# 03_-_CONNECTORS.net
KiCad netlist of a schematic drawn in Altium Designer
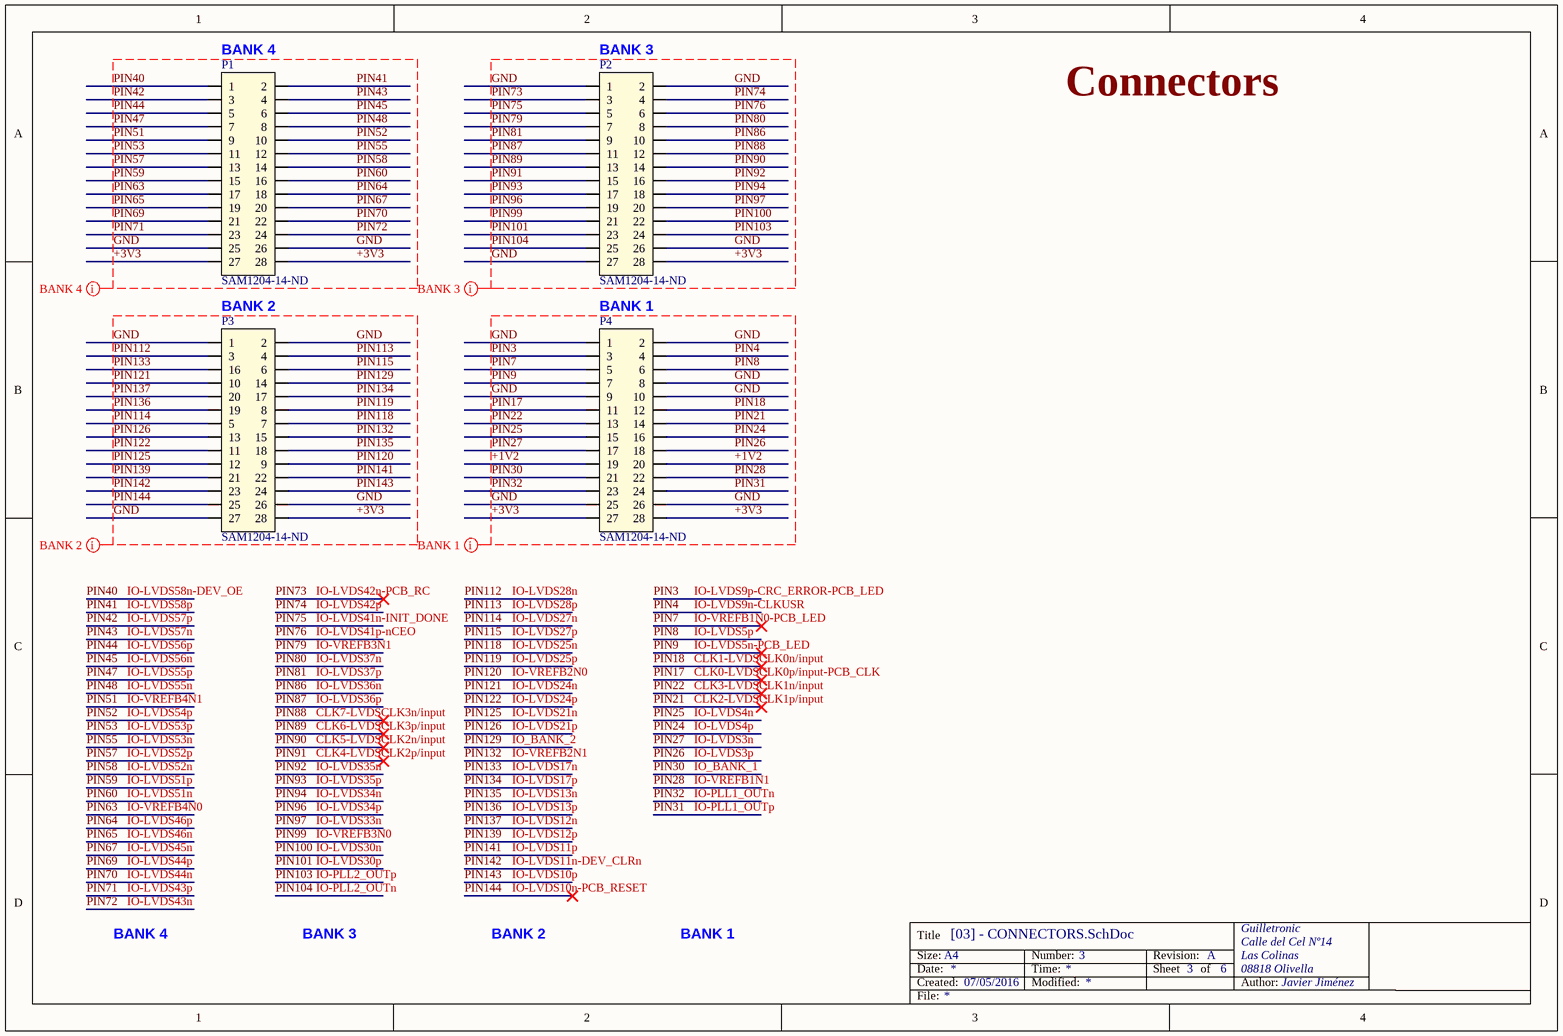
[diagram p0: [03] - CONNECTORS.SchDoc]

(export (version "E")
  (design (tool "Eeschema 10.0.6"))
  (components
    (comp (ref "P1")
      (value "Female Header 14x2 2.54mm 10mm")
      (footprint "Female Header 14x2 2.54mm 10mm")
      (description "ELEVATED SOCKET STRIPS")
      (fields (field (name "SUPPLIER PART NUMBER 1") "SAM1204-14-ND"))
      (libsource (lib "GUILLETRONIC") (part "Female Header 14x2 2.54mm 10mm"))
    )
    (comp (ref "P2")
      (value "Female Header 14x2 2.54mm 10mm")
      (footprint "Female Header 14x2 2.54mm 10mm")
      (description "ELEVATED SOCKET STRIPS")
      (fields (field (name "SUPPLIER PART NUMBER 1") "SAM1204-14-ND"))
      (libsource (lib "GUILLETRONIC") (part "Female Header 14x2 2.54mm 10mm"))
    )
    (comp (ref "P3")
      (value "Female Header 14x2 2.54mm 10mm")
      (footprint "Female Header 14x2 2.54mm 10mm")
      (description "ELEVATED SOCKET STRIPS")
      (fields (field (name "SUPPLIER PART NUMBER 1") "SAM1204-14-ND"))
      (libsource (lib "") (part "Female Header 14x2 2.54mm 10mm_1"))
    )
    (comp (ref "P4")
      (value "Female Header 14x2 2.54mm 10mm")
      (footprint "Female Header 14x2 2.54mm 10mm")
      (description "ELEVATED SOCKET STRIPS")
      (fields (field (name "SUPPLIER PART NUMBER 1") "SAM1204-14-ND"))
      (libsource (lib "GUILLETRONIC") (part "Female Header 14x2 2.54mm 10mm"))
    )
  )
  (nets
    (net (code "1") (name "/+1V2") (class "Default")
      (node (ref "P4") (pin "19") (pinfunction "19_19") (pintype "passive"))
      (node (ref "P4") (pin "20") (pinfunction "20_20") (pintype "passive"))
    )
    (net (code "2") (name "/+3V3") (class "Default")
      (node (ref "P1") (pin "27") (pinfunction "27_27") (pintype "passive"))
      (node (ref "P1") (pin "28") (pinfunction "28_28") (pintype "passive"))
      (node (ref "P2") (pin "28") (pinfunction "28_28") (pintype "passive"))
      (node (ref "P3") (pin "28") (pinfunction "28_28") (pintype "passive"))
      (node (ref "P4") (pin "27") (pinfunction "27_27") (pintype "passive"))
      (node (ref "P4") (pin "28") (pinfunction "28_28") (pintype "passive"))
    )
    (net (code "3") (name "/GND") (class "Default")
      (node (ref "P1") (pin "25") (pinfunction "25_25") (pintype "passive"))
      (node (ref "P1") (pin "26") (pinfunction "26_26") (pintype "passive"))
      (node (ref "P2") (pin "1") (pinfunction "1_1") (pintype "passive"))
      (node (ref "P2") (pin "2") (pinfunction "2_2") (pintype "passive"))
      (node (ref "P2") (pin "26") (pinfunction "26_26") (pintype "passive"))
      (node (ref "P2") (pin "27") (pinfunction "27_27") (pintype "passive"))
      (node (ref "P3") (pin "1") (pinfunction "1_1") (pintype "passive"))
      (node (ref "P3") (pin "2") (pinfunction "2_2") (pintype "passive"))
      (node (ref "P3") (pin "26") (pinfunction "26_26") (pintype "passive"))
      (node (ref "P3") (pin "27") (pinfunction "27_27") (pintype "passive"))
      (node (ref "P4") (pin "1") (pinfunction "1_1") (pintype "passive"))
      (node (ref "P4") (pin "10") (pinfunction "10_10") (pintype "passive"))
      (node (ref "P4") (pin "2") (pinfunction "2_2") (pintype "passive"))
      (node (ref "P4") (pin "25") (pinfunction "25_25") (pintype "passive"))
      (node (ref "P4") (pin "26") (pinfunction "26_26") (pintype "passive"))
      (node (ref "P4") (pin "8") (pinfunction "8_8") (pintype "passive"))
      (node (ref "P4") (pin "9") (pinfunction "9_9") (pintype "passive"))
    )
    (net (code "4") (name "/PIN3") (class "Default")
      (node (ref "P4") (pin "3") (pinfunction "3_3") (pintype "passive"))
    )
    (net (code "5") (name "/PIN4") (class "Default")
      (node (ref "P4") (pin "4") (pinfunction "4_4") (pintype "passive"))
    )
    (net (code "6") (name "/PIN7") (class "Default")
      (node (ref "P4") (pin "5") (pinfunction "5_5") (pintype "passive+no_connect"))
    )
    (net (code "7") (name "/PIN8") (class "Default")
      (node (ref "P4") (pin "6") (pinfunction "6_6") (pintype "passive"))
    )
    (net (code "8") (name "/PIN9") (class "Default")
      (node (ref "P4") (pin "7") (pinfunction "7_7") (pintype "passive+no_connect"))
    )
    (net (code "9") (name "/PIN17") (class "Default")
      (node (ref "P4") (pin "11") (pinfunction "11_11") (pintype "passive+no_connect"))
    )
    (net (code "10") (name "/PIN18") (class "Default")
      (node (ref "P4") (pin "12") (pinfunction "12_12") (pintype "passive+no_connect"))
    )
    (net (code "11") (name "/PIN21") (class "Default")
      (node (ref "P4") (pin "14") (pinfunction "14_14") (pintype "passive+no_connect"))
    )
    (net (code "12") (name "/PIN22") (class "Default")
      (node (ref "P4") (pin "13") (pinfunction "13_13") (pintype "passive+no_connect"))
    )
    (net (code "13") (name "/PIN24") (class "Default")
      (node (ref "P4") (pin "16") (pinfunction "16_16") (pintype "passive"))
    )
    (net (code "14") (name "/PIN25") (class "Default")
      (node (ref "P4") (pin "15") (pinfunction "15_15") (pintype "passive"))
    )
    (net (code "15") (name "/PIN26") (class "Default")
      (node (ref "P4") (pin "18") (pinfunction "18_18") (pintype "passive"))
    )
    (net (code "16") (name "/PIN27") (class "Default")
      (node (ref "P4") (pin "17") (pinfunction "17_17") (pintype "passive"))
    )
    (net (code "17") (name "/PIN28") (class "Default")
      (node (ref "P4") (pin "22") (pinfunction "22_22") (pintype "passive"))
    )
    (net (code "18") (name "/PIN30") (class "Default")
      (node (ref "P4") (pin "21") (pinfunction "21_21") (pintype "passive"))
    )
    (net (code "19") (name "/PIN31") (class "Default")
      (node (ref "P4") (pin "24") (pinfunction "24_24") (pintype "passive"))
    )
    (net (code "20") (name "/PIN32") (class "Default")
      (node (ref "P4") (pin "23") (pinfunction "23_23") (pintype "passive"))
    )
    (net (code "21") (name "/PIN40") (class "Default")
      (node (ref "P1") (pin "1") (pinfunction "1_1") (pintype "passive"))
    )
    (net (code "22") (name "/PIN41") (class "Default")
      (node (ref "P1") (pin "2") (pinfunction "2_2") (pintype "passive"))
    )
    (net (code "23") (name "/PIN42") (class "Default")
      (node (ref "P1") (pin "3") (pinfunction "3_3") (pintype "passive"))
    )
    (net (code "24") (name "/PIN43") (class "Default")
      (node (ref "P1") (pin "4") (pinfunction "4_4") (pintype "passive"))
    )
    (net (code "25") (name "/PIN44") (class "Default")
      (node (ref "P1") (pin "5") (pinfunction "5_5") (pintype "passive"))
    )
    (net (code "26") (name "/PIN45") (class "Default")
      (node (ref "P1") (pin "6") (pinfunction "6_6") (pintype "passive"))
    )
    (net (code "27") (name "/PIN47") (class "Default")
      (node (ref "P1") (pin "7") (pinfunction "7_7") (pintype "passive"))
    )
    (net (code "28") (name "/PIN48") (class "Default")
      (node (ref "P1") (pin "8") (pinfunction "8_8") (pintype "passive"))
    )
    (net (code "29") (name "/PIN51") (class "Default")
      (node (ref "P1") (pin "9") (pinfunction "9_9") (pintype "passive"))
    )
    (net (code "30") (name "/PIN52") (class "Default")
      (node (ref "P1") (pin "10") (pinfunction "10_10") (pintype "passive"))
    )
    (net (code "31") (name "/PIN53") (class "Default")
      (node (ref "P1") (pin "11") (pinfunction "11_11") (pintype "passive"))
    )
    (net (code "32") (name "/PIN55") (class "Default")
      (node (ref "P1") (pin "12") (pinfunction "12_12") (pintype "passive"))
    )
    (net (code "33") (name "/PIN57") (class "Default")
      (node (ref "P1") (pin "13") (pinfunction "13_13") (pintype "passive"))
    )
    (net (code "34") (name "/PIN58") (class "Default")
      (node (ref "P1") (pin "14") (pinfunction "14_14") (pintype "passive"))
    )
    (net (code "35") (name "/PIN59") (class "Default")
      (node (ref "P1") (pin "15") (pinfunction "15_15") (pintype "passive"))
    )
    (net (code "36") (name "/PIN60") (class "Default")
      (node (ref "P1") (pin "16") (pinfunction "16_16") (pintype "passive"))
    )
    (net (code "37") (name "/PIN63") (class "Default")
      (node (ref "P1") (pin "17") (pinfunction "17_17") (pintype "passive"))
    )
    (net (code "38") (name "/PIN64") (class "Default")
      (node (ref "P1") (pin "18") (pinfunction "18_18") (pintype "passive"))
    )
    (net (code "39") (name "/PIN65") (class "Default")
      (node (ref "P1") (pin "19") (pinfunction "19_19") (pintype "passive"))
    )
    (net (code "40") (name "/PIN67") (class "Default")
      (node (ref "P1") (pin "20") (pinfunction "20_20") (pintype "passive"))
    )
    (net (code "41") (name "/PIN69") (class "Default")
      (node (ref "P1") (pin "21") (pinfunction "21_21") (pintype "passive"))
    )
    (net (code "42") (name "/PIN70") (class "Default")
      (node (ref "P1") (pin "22") (pinfunction "22_22") (pintype "passive"))
    )
    (net (code "43") (name "/PIN71") (class "Default")
      (node (ref "P1") (pin "23") (pinfunction "23_23") (pintype "passive"))
    )
    (net (code "44") (name "/PIN72") (class "Default")
      (node (ref "P1") (pin "24") (pinfunction "24_24") (pintype "passive"))
    )
    (net (code "45") (name "/PIN73") (class "Default")
      (node (ref "P2") (pin "3") (pinfunction "3_3") (pintype "passive"))
    )
    (net (code "46") (name "/PIN74") (class "Default")
      (node (ref "P2") (pin "4") (pinfunction "4_4") (pintype "passive"))
    )
    (net (code "47") (name "/PIN75") (class "Default")
      (node (ref "P2") (pin "5") (pinfunction "5_5") (pintype "passive"))
    )
    (net (code "48") (name "/PIN76") (class "Default")
      (node (ref "P2") (pin "6") (pinfunction "6_6") (pintype "passive"))
    )
    (net (code "49") (name "/PIN79") (class "Default")
      (node (ref "P2") (pin "7") (pinfunction "7_7") (pintype "passive"))
    )
    (net (code "50") (name "/PIN80") (class "Default")
      (node (ref "P2") (pin "8") (pinfunction "8_8") (pintype "passive"))
    )
    (net (code "51") (name "/PIN81") (class "Default")
      (node (ref "P2") (pin "9") (pinfunction "9_9") (pintype "passive"))
    )
    (net (code "52") (name "/PIN86") (class "Default")
      (node (ref "P2") (pin "10") (pinfunction "10_10") (pintype "passive"))
    )
    (net (code "53") (name "/PIN87") (class "Default")
      (node (ref "P2") (pin "11") (pinfunction "11_11") (pintype "passive"))
    )
    (net (code "54") (name "/PIN88") (class "Default")
      (node (ref "P2") (pin "12") (pinfunction "12_12") (pintype "passive+no_connect"))
    )
    (net (code "55") (name "/PIN89") (class "Default")
      (node (ref "P2") (pin "13") (pinfunction "13_13") (pintype "passive"))
    )
    (net (code "56") (name "/PIN90") (class "Default")
      (node (ref "P2") (pin "14") (pinfunction "14_14") (pintype "passive+no_connect"))
    )
    (net (code "57") (name "/PIN91") (class "Default")
      (node (ref "P2") (pin "15") (pinfunction "15_15") (pintype "passive"))
    )
    (net (code "58") (name "/PIN92") (class "Default")
      (node (ref "P2") (pin "16") (pinfunction "16_16") (pintype "passive"))
    )
    (net (code "59") (name "/PIN93") (class "Default")
      (node (ref "P2") (pin "17") (pinfunction "17_17") (pintype "passive"))
    )
    (net (code "60") (name "/PIN94") (class "Default")
      (node (ref "P2") (pin "18") (pinfunction "18_18") (pintype "passive"))
    )
    (net (code "61") (name "/PIN96") (class "Default")
      (node (ref "P2") (pin "19") (pinfunction "19_19") (pintype "passive"))
    )
    (net (code "62") (name "/PIN97") (class "Default")
      (node (ref "P2") (pin "20") (pinfunction "20_20") (pintype "passive"))
    )
    (net (code "63") (name "/PIN99") (class "Default")
      (node (ref "P2") (pin "21") (pinfunction "21_21") (pintype "passive"))
    )
    (net (code "64") (name "/PIN100") (class "Default")
      (node (ref "P2") (pin "22") (pinfunction "22_22") (pintype "passive"))
    )
    (net (code "65") (name "/PIN101") (class "Default")
      (node (ref "P2") (pin "23") (pinfunction "23_23") (pintype "passive"))
    )
    (net (code "66") (name "/PIN103") (class "Default")
      (node (ref "P2") (pin "24") (pinfunction "24_24") (pintype "passive"))
    )
    (net (code "67") (name "/PIN104") (class "Default")
      (node (ref "P2") (pin "25") (pinfunction "25_25") (pintype "passive"))
    )
    (net (code "68") (name "/PIN112") (class "Default")
      (node (ref "P3") (pin "3") (pinfunction "3_3") (pintype "passive"))
    )
    (net (code "69") (name "/PIN113") (class "Default")
      (node (ref "P3") (pin "4") (pinfunction "4_4") (pintype "passive"))
    )
    (net (code "70") (name "/PIN114") (class "Default")
      (node (ref "P3") (pin "5") (pinfunction "5_5") (pintype "passive"))
    )
    (net (code "71") (name "/PIN115") (class "Default")
      (node (ref "P3") (pin "6") (pinfunction "6_6") (pintype "passive"))
    )
    (net (code "72") (name "/PIN118") (class "Default")
      (node (ref "P3") (pin "7") (pinfunction "7_7") (pintype "passive"))
    )
    (net (code "73") (name "/PIN119") (class "Default")
      (node (ref "P3") (pin "8") (pinfunction "8_8") (pintype "passive"))
    )
    (net (code "74") (name "/PIN120") (class "Default")
      (node (ref "P3") (pin "9") (pinfunction "9_9") (pintype "passive"))
    )
    (net (code "75") (name "/PIN121") (class "Default")
      (node (ref "P3") (pin "10") (pinfunction "10_10") (pintype "passive"))
    )
    (net (code "76") (name "/PIN122") (class "Default")
      (node (ref "P3") (pin "11") (pinfunction "11_11") (pintype "passive"))
    )
    (net (code "77") (name "/PIN125") (class "Default")
      (node (ref "P3") (pin "12") (pinfunction "12_12") (pintype "passive"))
    )
    (net (code "78") (name "/PIN126") (class "Default")
      (node (ref "P3") (pin "13") (pinfunction "13_13") (pintype "passive"))
    )
    (net (code "79") (name "/PIN129") (class "Default")
      (node (ref "P3") (pin "14") (pinfunction "14_14") (pintype "passive"))
    )
    (net (code "80") (name "/PIN132") (class "Default")
      (node (ref "P3") (pin "15") (pinfunction "15_15") (pintype "passive"))
    )
    (net (code "81") (name "/PIN133") (class "Default")
      (node (ref "P3") (pin "16") (pinfunction "16_16") (pintype "passive"))
    )
    (net (code "82") (name "/PIN134") (class "Default")
      (node (ref "P3") (pin "17") (pinfunction "17_17") (pintype "passive"))
    )
    (net (code "83") (name "/PIN135") (class "Default")
      (node (ref "P3") (pin "18") (pinfunction "18_18") (pintype "passive"))
    )
    (net (code "84") (name "/PIN136") (class "Default")
      (node (ref "P3") (pin "19") (pinfunction "19_19") (pintype "passive"))
    )
    (net (code "85") (name "/PIN137") (class "Default")
      (node (ref "P3") (pin "20") (pinfunction "20_20") (pintype "passive"))
    )
    (net (code "86") (name "/PIN139") (class "Default")
      (node (ref "P3") (pin "21") (pinfunction "21_21") (pintype "passive"))
    )
    (net (code "87") (name "/PIN141") (class "Default")
      (node (ref "P3") (pin "22") (pinfunction "22_22") (pintype "passive"))
    )
    (net (code "88") (name "/PIN142") (class "Default")
      (node (ref "P3") (pin "23") (pinfunction "23_23") (pintype "passive"))
    )
    (net (code "89") (name "/PIN143") (class "Default")
      (node (ref "P3") (pin "24") (pinfunction "24_24") (pintype "passive"))
    )
    (net (code "90") (name "/PIN144") (class "Default")
      (node (ref "P3") (pin "25") (pinfunction "25_25") (pintype "passive+no_connect"))
    )
  )
)
